# arduipi_test_board.net
KiCad netlist of a schematic drawn in EAGLE
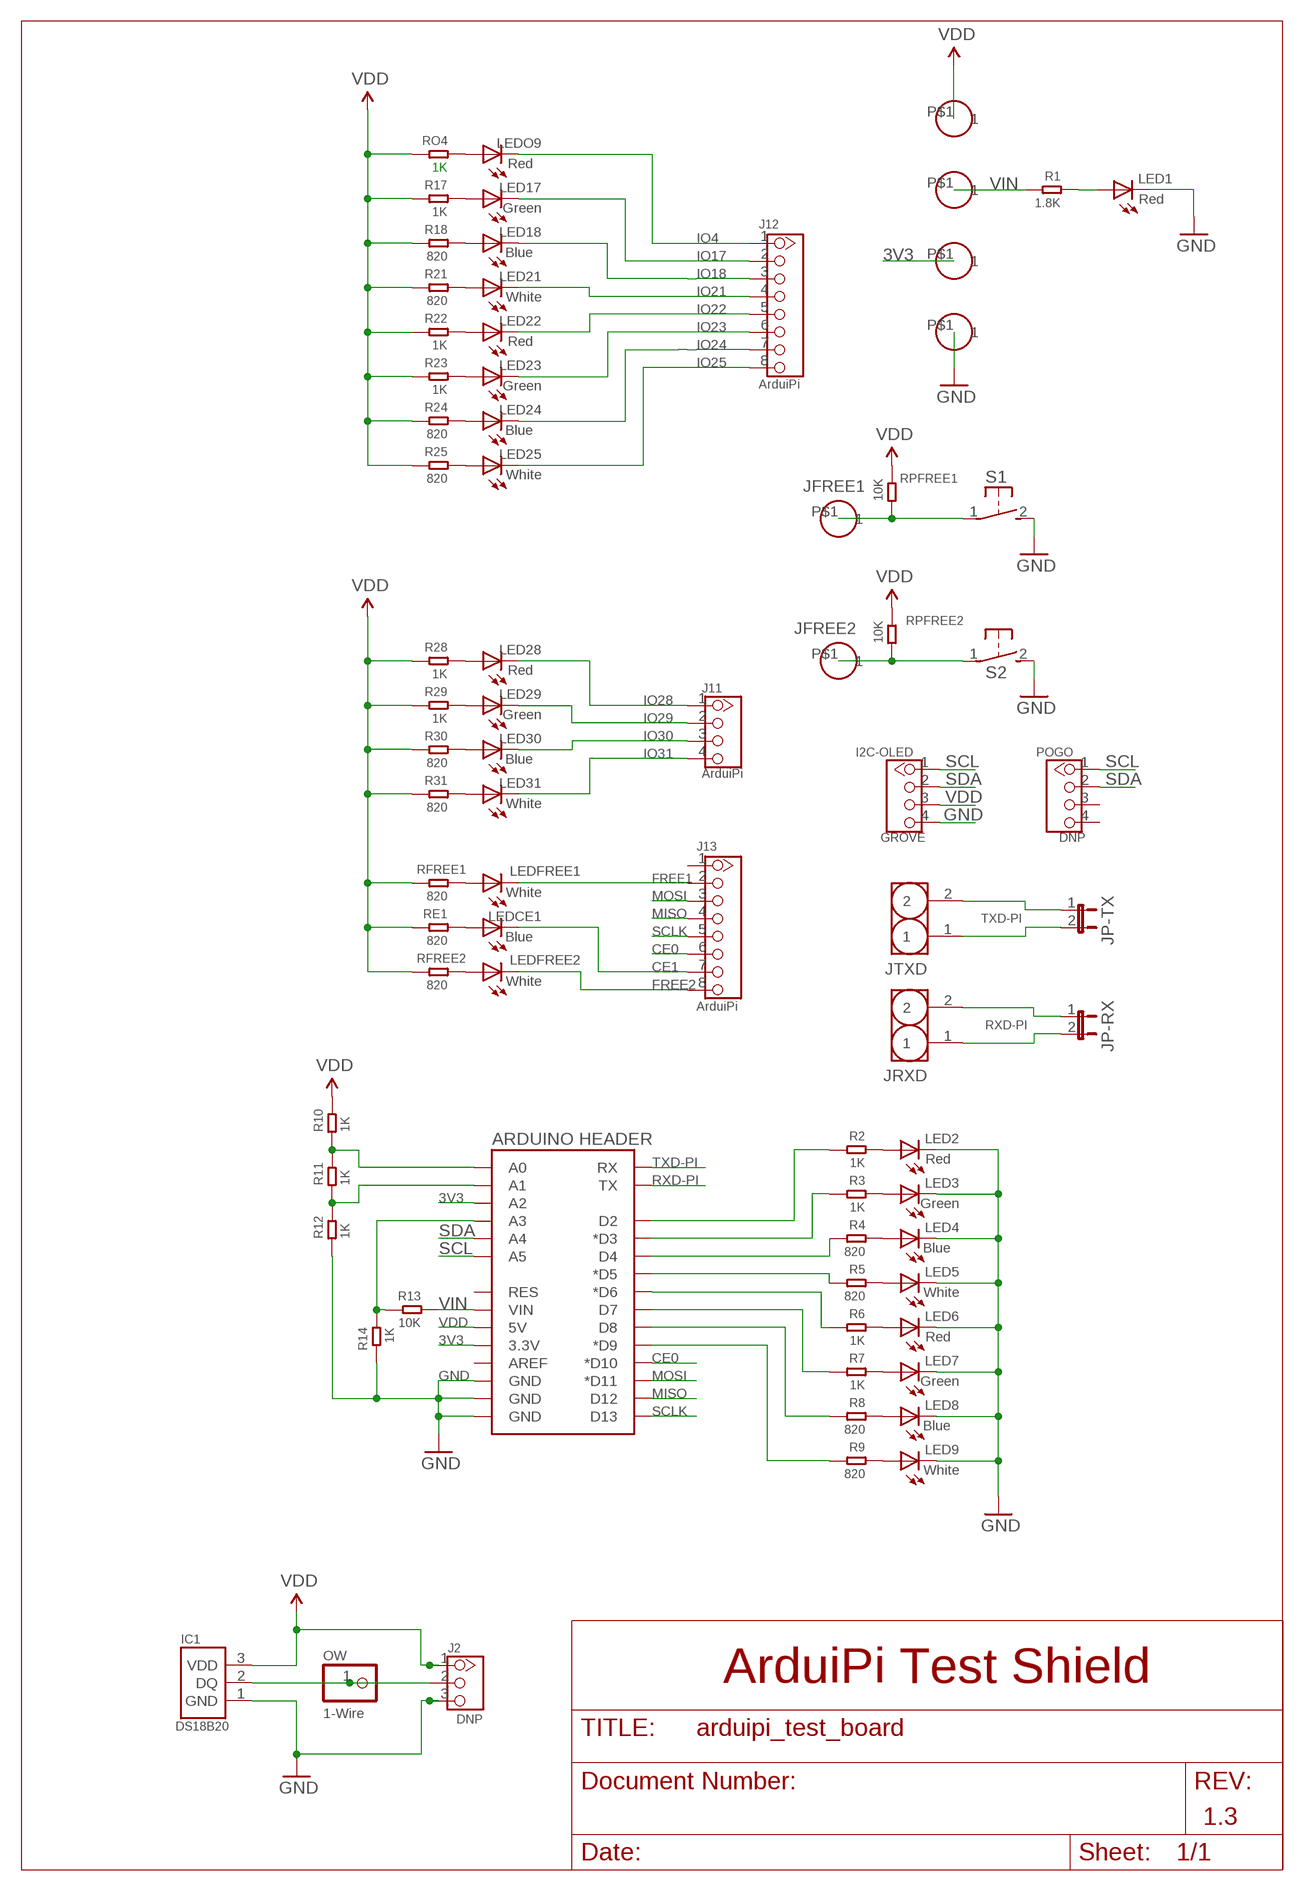
[diagram p0: schematic, sheet 1]

(export (version "E")
  (design (tool "Eeschema 10.0.6"))
  (components
    (comp (ref "3V3")
      (value "HEADER-1P-32")
      (footprint "eagle-import:1P-60_32MIL")
      (libsource (lib "eagle-import") (part "HEADER-1P-32"))
    )
    (comp (ref "GND")
      (value "HEADER-1P-32")
      (footprint "eagle-import:1P-60_32MIL")
      (libsource (lib "eagle-import") (part "HEADER-1P-32"))
    )
    (comp (ref "I2C-OLED")
      (value "GROVE")
      (footprint "eagle-import:4P-LEADED-2.0")
      (libsource (lib "eagle-import") (part "TWIG-2.0-LEADED"))
    )
    (comp (ref "IC1")
      (value "DS18B20")
      (footprint "eagle-import:TO-92-TRIANGLE")
      (libsource (lib "eagle-import") (part "SENSOR-DS18B20"))
    )
    (comp (ref "J2")
      (value "DNP")
      (footprint "eagle-import:3P-2.54")
      (libsource (lib "eagle-import") (part "HEADER-3P-2.54"))
    )
    (comp (ref "J11")
      (value "ArduiPi")
      (footprint "eagle-import:4P-2.54-80_40MIL")
      (libsource (lib "eagle-import") (part "HEADER-4P-80/40MIL"))
    )
    (comp (ref "J12")
      (value "ArduiPi")
      (footprint "eagle-import:8P-2.54-80_40MIL")
      (libsource (lib "eagle-import") (part "HEADER-8P-80/40MIL"))
    )
    (comp (ref "J13")
      (value "ArduiPi")
      (footprint "eagle-import:8P-2.54-80_40MIL")
      (libsource (lib "eagle-import") (part "HEADER-8P-80/40MIL"))
    )
    (comp (ref "JFREE1")
      (value "HEADER-1P-32")
      (footprint "eagle-import:1P-60_32MIL")
      (libsource (lib "eagle-import") (part "HEADER-1P-32"))
    )
    (comp (ref "JFREE2")
      (value "HEADER-1P-32")
      (footprint "eagle-import:1P-60_32MIL")
      (libsource (lib "eagle-import") (part "HEADER-1P-32"))
    )
    (comp (ref "JP-RX")
      (value "JUMPER-2PTH")
      (footprint "eagle-import:1X02")
      (libsource (lib "eagle-import") (part "JUMPER-2PTH"))
    )
    (comp (ref "JP-TX")
      (value "JUMPER-2PTH")
      (footprint "eagle-import:1X02")
      (libsource (lib "eagle-import") (part "JUMPER-2PTH"))
    )
    (comp (ref "JRXD")
      (value "J2")
      (footprint "eagle-import:2P-2.54")
      (libsource (lib "eagle-import") (part "HEADER-2P-2.54"))
    )
    (comp (ref "JTXD")
      (value "J1")
      (footprint "eagle-import:2P-2.54")
      (libsource (lib "eagle-import") (part "HEADER-2P-2.54"))
    )
    (comp (ref "LED1")
      (value "Red")
      (footprint "eagle-import:LED3MM")
      (libsource (lib "eagle-import") (part "LED3MM"))
    )
    (comp (ref "LED2")
      (value "Red")
      (footprint "eagle-import:LED3MM")
      (libsource (lib "eagle-import") (part "LED3MM"))
    )
    (comp (ref "LED3")
      (value "Green")
      (footprint "eagle-import:LED3MM")
      (libsource (lib "eagle-import") (part "LED3MM"))
    )
    (comp (ref "LED4")
      (value "Blue")
      (footprint "eagle-import:LED3MM")
      (libsource (lib "eagle-import") (part "LED3MM"))
    )
    (comp (ref "LED5")
      (value "White")
      (footprint "eagle-import:LED3MM")
      (libsource (lib "eagle-import") (part "LED3MM"))
    )
    (comp (ref "LED6")
      (value "Red")
      (footprint "eagle-import:LED3MM")
      (libsource (lib "eagle-import") (part "LED3MM"))
    )
    (comp (ref "LED7")
      (value "Green")
      (footprint "eagle-import:LED3MM")
      (libsource (lib "eagle-import") (part "LED3MM"))
    )
    (comp (ref "LED8")
      (value "Blue")
      (footprint "eagle-import:LED3MM")
      (libsource (lib "eagle-import") (part "LED3MM"))
    )
    (comp (ref "LED9")
      (value "White")
      (footprint "eagle-import:LED3MM")
      (libsource (lib "eagle-import") (part "LED3MM"))
    )
    (comp (ref "LED17")
      (value "Green")
      (footprint "eagle-import:LED3MM")
      (libsource (lib "eagle-import") (part "LED3MM"))
    )
    (comp (ref "LED18")
      (value "Blue")
      (footprint "eagle-import:LED3MM")
      (libsource (lib "eagle-import") (part "LED3MM"))
    )
    (comp (ref "LED21")
      (value "White")
      (footprint "eagle-import:LED3MM")
      (libsource (lib "eagle-import") (part "LED3MM"))
    )
    (comp (ref "LED22")
      (value "Red")
      (footprint "eagle-import:LED3MM")
      (libsource (lib "eagle-import") (part "LED3MM"))
    )
    (comp (ref "LED23")
      (value "Green")
      (footprint "eagle-import:LED3MM")
      (libsource (lib "eagle-import") (part "LED3MM"))
    )
    (comp (ref "LED24")
      (value "Blue")
      (footprint "eagle-import:LED3MM")
      (libsource (lib "eagle-import") (part "LED3MM"))
    )
    (comp (ref "LED25")
      (value "White")
      (footprint "eagle-import:LED3MM")
      (libsource (lib "eagle-import") (part "LED3MM"))
    )
    (comp (ref "LED28")
      (value "Red")
      (footprint "eagle-import:LED3MM")
      (libsource (lib "eagle-import") (part "LED3MM"))
    )
    (comp (ref "LED29")
      (value "Green")
      (footprint "eagle-import:LED3MM")
      (libsource (lib "eagle-import") (part "LED3MM"))
    )
    (comp (ref "LED30")
      (value "Blue")
      (footprint "eagle-import:LED3MM")
      (libsource (lib "eagle-import") (part "LED3MM"))
    )
    (comp (ref "LED31")
      (value "White")
      (footprint "eagle-import:LED3MM")
      (libsource (lib "eagle-import") (part "LED3MM"))
    )
    (comp (ref "LEDCE1")
      (value "Blue")
      (footprint "eagle-import:LED3MM")
      (libsource (lib "eagle-import") (part "LED3MM"))
    )
    (comp (ref "LEDFREE1")
      (value "White")
      (footprint "eagle-import:LED3MM")
      (libsource (lib "eagle-import") (part "LED3MM"))
    )
    (comp (ref "LEDFREE2")
      (value "White")
      (footprint "eagle-import:LED3MM")
      (libsource (lib "eagle-import") (part "LED3MM"))
    )
    (comp (ref "LEDO9")
      (value "Red")
      (footprint "eagle-import:LED3MM")
      (libsource (lib "eagle-import") (part "LED3MM"))
    )
    (comp (ref "OW")
      (value "1-Wire")
      (footprint "eagle-import:1X01")
      (libsource (lib "eagle-import") (part "PINHD-1X1"))
    )
    (comp (ref "POGO")
      (value "DNP")
      (footprint "eagle-import:4P-LEADED-2.0")
      (libsource (lib "eagle-import") (part "TWIG-2.0-LEADED"))
    )
    (comp (ref "R1")
      (value "1.8K")
      (footprint "eagle-import:0204_7")
      (libsource (lib "eagle-import") (part "R-0204/7"))
    )
    (comp (ref "R2")
      (value "1K")
      (footprint "eagle-import:0204_7")
      (libsource (lib "eagle-import") (part "R-0204/7"))
    )
    (comp (ref "R3")
      (value "1K")
      (footprint "eagle-import:0204_7")
      (libsource (lib "eagle-import") (part "R-0204/7"))
    )
    (comp (ref "R4")
      (value "820")
      (footprint "eagle-import:0204_7")
      (libsource (lib "eagle-import") (part "R-0204/7"))
    )
    (comp (ref "R5")
      (value "820")
      (footprint "eagle-import:0204_7")
      (libsource (lib "eagle-import") (part "R-0204/7"))
    )
    (comp (ref "R6")
      (value "1K")
      (footprint "eagle-import:0204_7")
      (libsource (lib "eagle-import") (part "R-0204/7"))
    )
    (comp (ref "R7")
      (value "1K")
      (footprint "eagle-import:0204_7")
      (libsource (lib "eagle-import") (part "R-0204/7"))
    )
    (comp (ref "R8")
      (value "820")
      (footprint "eagle-import:0204_7")
      (libsource (lib "eagle-import") (part "R-0204/7"))
    )
    (comp (ref "R9")
      (value "820")
      (footprint "eagle-import:0204_7")
      (libsource (lib "eagle-import") (part "R-0204/7"))
    )
    (comp (ref "R10")
      (value "1K")
      (footprint "eagle-import:0204_7")
      (libsource (lib "eagle-import") (part "R-0204/7"))
    )
    (comp (ref "R11")
      (value "1K")
      (footprint "eagle-import:0204_7")
      (libsource (lib "eagle-import") (part "R-0204/7"))
    )
    (comp (ref "R12")
      (value "1K")
      (footprint "eagle-import:0204_7")
      (libsource (lib "eagle-import") (part "R-0204/7"))
    )
    (comp (ref "R13")
      (value "10K")
      (footprint "eagle-import:0204_7")
      (libsource (lib "eagle-import") (part "R-0204/7"))
    )
    (comp (ref "R14")
      (value "1K")
      (footprint "eagle-import:0204_7")
      (libsource (lib "eagle-import") (part "R-0204/7"))
    )
    (comp (ref "R17")
      (value "1K")
      (footprint "eagle-import:0204_7")
      (libsource (lib "eagle-import") (part "R-0204/7"))
    )
    (comp (ref "R18")
      (value "820")
      (footprint "eagle-import:0204_7")
      (libsource (lib "eagle-import") (part "R-0204/7"))
    )
    (comp (ref "R21")
      (value "820")
      (footprint "eagle-import:0204_7")
      (libsource (lib "eagle-import") (part "R-0204/7"))
    )
    (comp (ref "R22")
      (value "1K")
      (footprint "eagle-import:0204_7")
      (libsource (lib "eagle-import") (part "R-0204/7"))
    )
    (comp (ref "R23")
      (value "1K")
      (footprint "eagle-import:0204_7")
      (libsource (lib "eagle-import") (part "R-0204/7"))
    )
    (comp (ref "R24")
      (value "820")
      (footprint "eagle-import:0204_7")
      (libsource (lib "eagle-import") (part "R-0204/7"))
    )
    (comp (ref "R25")
      (value "820")
      (footprint "eagle-import:0204_7")
      (libsource (lib "eagle-import") (part "R-0204/7"))
    )
    (comp (ref "R28")
      (value "1K")
      (footprint "eagle-import:0204_7")
      (libsource (lib "eagle-import") (part "R-0204/7"))
    )
    (comp (ref "R29")
      (value "1K")
      (footprint "eagle-import:0204_7")
      (libsource (lib "eagle-import") (part "R-0204/7"))
    )
    (comp (ref "R30")
      (value "820")
      (footprint "eagle-import:0204_7")
      (libsource (lib "eagle-import") (part "R-0204/7"))
    )
    (comp (ref "R31")
      (value "820")
      (footprint "eagle-import:0204_7")
      (libsource (lib "eagle-import") (part "R-0204/7"))
    )
    (comp (ref "RE1")
      (value "820")
      (footprint "eagle-import:0204_7")
      (libsource (lib "eagle-import") (part "R-0204/7"))
    )
    (comp (ref "RFREE1")
      (value "820")
      (footprint "eagle-import:0204_7")
      (libsource (lib "eagle-import") (part "R-0204/7"))
    )
    (comp (ref "RFREE2")
      (value "820")
      (footprint "eagle-import:0204_7")
      (libsource (lib "eagle-import") (part "R-0204/7"))
    )
    (comp (ref "RO4")
      (value "1K")
      (footprint "eagle-import:0204_7")
      (libsource (lib "eagle-import") (part "R-0204/7"))
    )
    (comp (ref "RPFREE1")
      (value "10K")
      (footprint "eagle-import:0204_7")
      (libsource (lib "eagle-import") (part "R-0204/7"))
    )
    (comp (ref "RPFREE2")
      (value "10K")
      (footprint "eagle-import:0204_7")
      (libsource (lib "eagle-import") (part "R-0204/7"))
    )
    (comp (ref "S1")
      (value "DTS-3")
      (footprint "eagle-import:DTS-3")
      (libsource (lib "eagle-import") (part "DTS-3"))
    )
    (comp (ref "S2")
      (value "DTS-3")
      (footprint "eagle-import:DTS-3")
      (libsource (lib "eagle-import") (part "DTS-3"))
    )
    (comp (ref "U1")
      (value "ARDUINO HEADER")
      (footprint "eagle-import:DUEMILANOVE_VIAS")
      (libsource (lib "eagle-import") (part "ARDUINO_SHIELDNO_SILK"))
    )
    (comp (ref "VDD")
      (value "HEADER-1P-32")
      (footprint "eagle-import:1P-60_32MIL")
      (libsource (lib "eagle-import") (part "HEADER-1P-32"))
    )
    (comp (ref "VIN")
      (value "HEADER-1P-32")
      (footprint "eagle-import:1P-60_32MIL")
      (libsource (lib "eagle-import") (part "HEADER-1P-32"))
    )
  )
  (nets
    (net (code "1") (name "/3V3") (class "Default")
      (node (ref "3V3") (pin "P$1") (pinfunction "1_P$1") (pintype "bidirectional"))
      (node (ref "U1") (pin "3.3V") (pinfunction "3.3V_3.3V") (pintype "bidirectional"))
      (node (ref "U1") (pin "A2") (pinfunction "A2_A2") (pintype "bidirectional"))
    )
    (net (code "2") (name "/CE0") (class "Default")
      (node (ref "J13") (pin "6") (pinfunction "6_6") (pintype "bidirectional"))
      (node (ref "U1") (pin "D10") (pinfunction "*D10_D10") (pintype "bidirectional"))
    )
    (net (code "3") (name "/CE1") (class "Default")
      (node (ref "J13") (pin "7") (pinfunction "7_7") (pintype "bidirectional"))
      (node (ref "LEDCE1") (pin "K") (pinfunction "C_K") (pintype "passive"))
    )
    (net (code "4") (name "/FREE1") (class "Default")
      (node (ref "J13") (pin "2") (pinfunction "2_2") (pintype "bidirectional"))
      (node (ref "LEDFREE1") (pin "K") (pinfunction "C_K") (pintype "passive"))
    )
    (net (code "5") (name "/FREE2") (class "Default")
      (node (ref "J13") (pin "8") (pinfunction "8_8") (pintype "bidirectional"))
      (node (ref "LEDFREE2") (pin "K") (pinfunction "C_K") (pintype "passive"))
    )
    (net (code "6") (name "/IO4") (class "Default")
      (node (ref "J12") (pin "1") (pinfunction "1_1") (pintype "bidirectional"))
      (node (ref "LEDO9") (pin "K") (pinfunction "C_K") (pintype "passive"))
    )
    (net (code "7") (name "/IO17") (class "Default")
      (node (ref "J12") (pin "2") (pinfunction "2_2") (pintype "bidirectional"))
      (node (ref "LED17") (pin "K") (pinfunction "C_K") (pintype "passive"))
    )
    (net (code "8") (name "/IO18") (class "Default")
      (node (ref "J12") (pin "3") (pinfunction "3_3") (pintype "bidirectional"))
      (node (ref "LED18") (pin "K") (pinfunction "C_K") (pintype "passive"))
    )
    (net (code "9") (name "/IO21") (class "Default")
      (node (ref "J12") (pin "4") (pinfunction "4_4") (pintype "bidirectional"))
      (node (ref "LED21") (pin "K") (pinfunction "C_K") (pintype "passive"))
    )
    (net (code "10") (name "/IO22") (class "Default")
      (node (ref "J12") (pin "5") (pinfunction "5_5") (pintype "bidirectional"))
      (node (ref "LED22") (pin "K") (pinfunction "C_K") (pintype "passive"))
    )
    (net (code "11") (name "/IO23") (class "Default")
      (node (ref "J12") (pin "6") (pinfunction "6_6") (pintype "bidirectional"))
      (node (ref "LED23") (pin "K") (pinfunction "C_K") (pintype "passive"))
    )
    (net (code "12") (name "/IO24") (class "Default")
      (node (ref "J12") (pin "7") (pinfunction "7_7") (pintype "bidirectional"))
      (node (ref "LED24") (pin "K") (pinfunction "C_K") (pintype "passive"))
    )
    (net (code "13") (name "/IO25") (class "Default")
      (node (ref "J12") (pin "8") (pinfunction "8_8") (pintype "bidirectional"))
      (node (ref "LED25") (pin "K") (pinfunction "C_K") (pintype "passive"))
    )
    (net (code "14") (name "/IO28") (class "Default")
      (node (ref "J11") (pin "1") (pinfunction "P$1_1") (pintype "bidirectional"))
      (node (ref "LED28") (pin "K") (pinfunction "C_K") (pintype "passive"))
    )
    (net (code "15") (name "/IO29") (class "Default")
      (node (ref "J11") (pin "2") (pinfunction "P$2_2") (pintype "bidirectional"))
      (node (ref "LED29") (pin "K") (pinfunction "C_K") (pintype "passive"))
    )
    (net (code "16") (name "/IO30") (class "Default")
      (node (ref "J11") (pin "3") (pinfunction "P$3_3") (pintype "bidirectional"))
      (node (ref "LED30") (pin "K") (pinfunction "C_K") (pintype "passive"))
    )
    (net (code "17") (name "/IO31") (class "Default")
      (node (ref "J11") (pin "4") (pinfunction "P$4_4") (pintype "bidirectional"))
      (node (ref "LED31") (pin "K") (pinfunction "C_K") (pintype "passive"))
    )
    (net (code "18") (name "/MISO") (class "Default")
      (node (ref "J13") (pin "4") (pinfunction "4_4") (pintype "bidirectional"))
      (node (ref "U1") (pin "D12") (pinfunction "D12_D12") (pintype "bidirectional"))
    )
    (net (code "19") (name "/MOSI") (class "Default")
      (node (ref "J13") (pin "3") (pinfunction "3_3") (pintype "bidirectional"))
      (node (ref "U1") (pin "D11") (pinfunction "*D11_D11") (pintype "bidirectional"))
    )
    (net (code "20") (name "/RXD-PI") (class "Default")
      (node (ref "JP-RX") (pin "1") (pinfunction "1_1") (pintype "passive"))
      (node (ref "JRXD") (pin "2") (pinfunction "2_2") (pintype "bidirectional"))
      (node (ref "U1") (pin "TX") (pinfunction "TX_TX") (pintype "bidirectional"))
    )
    (net (code "21") (name "/SCL") (class "Default")
      (node (ref "I2C-OLED") (pin "1") (pinfunction "1_1") (pintype "bidirectional"))
      (node (ref "POGO") (pin "1") (pinfunction "1_1") (pintype "bidirectional"))
      (node (ref "U1") (pin "A5") (pinfunction "A5_A5") (pintype "bidirectional"))
    )
    (net (code "22") (name "/SCLK") (class "Default")
      (node (ref "J13") (pin "5") (pinfunction "5_5") (pintype "bidirectional"))
      (node (ref "U1") (pin "D13") (pinfunction "D13_D13") (pintype "bidirectional"))
    )
    (net (code "23") (name "/SDA") (class "Default")
      (node (ref "I2C-OLED") (pin "2") (pinfunction "2_2") (pintype "bidirectional"))
      (node (ref "POGO") (pin "2") (pinfunction "2_2") (pintype "bidirectional"))
      (node (ref "U1") (pin "A4") (pinfunction "A4_A4") (pintype "bidirectional"))
    )
    (net (code "24") (name "/TXD-PI") (class "Default")
      (node (ref "JP-TX") (pin "1") (pinfunction "1_1") (pintype "passive"))
      (node (ref "JTXD") (pin "2") (pinfunction "2_2") (pintype "bidirectional"))
      (node (ref "U1") (pin "RX") (pinfunction "RX_RX") (pintype "bidirectional"))
    )
    (net (code "25") (name "/VIN") (class "Default")
      (node (ref "R1") (pin "2") (pinfunction "2_2") (pintype "passive"))
      (node (ref "R13") (pin "1") (pinfunction "1_1") (pintype "passive"))
      (node (ref "U1") (pin "VIN") (pinfunction "VIN_VIN") (pintype "bidirectional"))
      (node (ref "VIN") (pin "P$1") (pinfunction "1_P$1") (pintype "bidirectional"))
    )
    (net (code "26") (name "GND") (class "Default")
      (node (ref "GND") (pin "P$1") (pinfunction "1_P$1") (pintype "bidirectional"))
      (node (ref "I2C-OLED") (pin "4") (pinfunction "4_4") (pintype "bidirectional"))
      (node (ref "IC1") (pin "1") (pinfunction "GND_1") (pintype "bidirectional"))
      (node (ref "J2") (pin "3") (pinfunction "P$3_3") (pintype "bidirectional"))
      (node (ref "LED1") (pin "K") (pinfunction "C_K") (pintype "passive"))
      (node (ref "LED2") (pin "K") (pinfunction "C_K") (pintype "passive"))
      (node (ref "LED3") (pin "K") (pinfunction "C_K") (pintype "passive"))
      (node (ref "LED4") (pin "K") (pinfunction "C_K") (pintype "passive"))
      (node (ref "LED5") (pin "K") (pinfunction "C_K") (pintype "passive"))
      (node (ref "LED6") (pin "K") (pinfunction "C_K") (pintype "passive"))
      (node (ref "LED7") (pin "K") (pinfunction "C_K") (pintype "passive"))
      (node (ref "LED8") (pin "K") (pinfunction "C_K") (pintype "passive"))
      (node (ref "LED9") (pin "K") (pinfunction "C_K") (pintype "passive"))
      (node (ref "R12") (pin "1") (pinfunction "1_1") (pintype "passive"))
      (node (ref "R14") (pin "2") (pinfunction "2_2") (pintype "passive"))
      (node (ref "S1") (pin "2") (pinfunction "2_2") (pintype "passive"))
      (node (ref "S2") (pin "2") (pinfunction "2_2") (pintype "passive"))
      (node (ref "U1") (pin "GND@0") (pinfunction "GND_GND@0") (pintype "bidirectional"))
      (node (ref "U1") (pin "GND@1") (pinfunction "GND_GND@1") (pintype "bidirectional"))
      (node (ref "U1") (pin "GND@2") (pinfunction "GND_GND@2") (pintype "bidirectional"))
    )
    (net (code "27") (name "Net-(IC1-DQ)") (class "Default")
      (node (ref "IC1") (pin "2") (pinfunction "DQ_2") (pintype "bidirectional"))
      (node (ref "J2") (pin "2") (pinfunction "P$2_2") (pintype "bidirectional"))
      (node (ref "OW") (pin "1") (pinfunction "1_1") (pintype "passive"))
    )
    (net (code "28") (name "Net-(JFREE1-1)") (class "Default")
      (node (ref "JFREE1") (pin "P$1") (pinfunction "1_P$1") (pintype "bidirectional"))
      (node (ref "RPFREE1") (pin "2") (pinfunction "2_2") (pintype "passive"))
      (node (ref "S1") (pin "1") (pinfunction "1_1") (pintype "passive"))
    )
    (net (code "29") (name "Net-(JFREE2-1)") (class "Default")
      (node (ref "JFREE2") (pin "P$1") (pinfunction "1_P$1") (pintype "bidirectional"))
      (node (ref "RPFREE2") (pin "1") (pinfunction "1_1") (pintype "passive"))
      (node (ref "S2") (pin "1") (pinfunction "1_1") (pintype "passive"))
    )
    (net (code "30") (name "Net-(JP-RX-Pad2)") (class "Default")
      (node (ref "JP-RX") (pin "2") (pinfunction "2_2") (pintype "passive"))
      (node (ref "JRXD") (pin "1") (pinfunction "1_1") (pintype "bidirectional"))
    )
    (net (code "31") (name "Net-(JP-TX-Pad2)") (class "Default")
      (node (ref "JP-TX") (pin "2") (pinfunction "2_2") (pintype "passive"))
      (node (ref "JTXD") (pin "1") (pinfunction "1_1") (pintype "bidirectional"))
    )
    (net (code "32") (name "Net-(LED1-PadA)") (class "Default")
      (node (ref "LED1") (pin "A") (pinfunction "A_A") (pintype "passive"))
      (node (ref "R1") (pin "1") (pinfunction "1_1") (pintype "passive"))
    )
    (net (code "33") (name "Net-(LED2-PadA)") (class "Default")
      (node (ref "LED2") (pin "A") (pinfunction "A_A") (pintype "passive"))
      (node (ref "R2") (pin "1") (pinfunction "1_1") (pintype "passive"))
    )
    (net (code "34") (name "Net-(LED3-PadA)") (class "Default")
      (node (ref "LED3") (pin "A") (pinfunction "A_A") (pintype "passive"))
      (node (ref "R3") (pin "1") (pinfunction "1_1") (pintype "passive"))
    )
    (net (code "35") (name "Net-(LED4-PadA)") (class "Default")
      (node (ref "LED4") (pin "A") (pinfunction "A_A") (pintype "passive"))
      (node (ref "R4") (pin "1") (pinfunction "1_1") (pintype "passive"))
    )
    (net (code "36") (name "Net-(LED5-PadA)") (class "Default")
      (node (ref "LED5") (pin "A") (pinfunction "A_A") (pintype "passive"))
      (node (ref "R5") (pin "1") (pinfunction "1_1") (pintype "passive"))
    )
    (net (code "37") (name "Net-(LED6-PadA)") (class "Default")
      (node (ref "LED6") (pin "A") (pinfunction "A_A") (pintype "passive"))
      (node (ref "R6") (pin "1") (pinfunction "1_1") (pintype "passive"))
    )
    (net (code "38") (name "Net-(LED7-PadA)") (class "Default")
      (node (ref "LED7") (pin "A") (pinfunction "A_A") (pintype "passive"))
      (node (ref "R7") (pin "1") (pinfunction "1_1") (pintype "passive"))
    )
    (net (code "39") (name "Net-(LED8-PadA)") (class "Default")
      (node (ref "LED8") (pin "A") (pinfunction "A_A") (pintype "passive"))
      (node (ref "R8") (pin "1") (pinfunction "1_1") (pintype "passive"))
    )
    (net (code "40") (name "Net-(LED9-PadA)") (class "Default")
      (node (ref "LED9") (pin "A") (pinfunction "A_A") (pintype "passive"))
      (node (ref "R9") (pin "1") (pinfunction "1_1") (pintype "passive"))
    )
    (net (code "41") (name "Net-(LED17-PadA)") (class "Default")
      (node (ref "LED17") (pin "A") (pinfunction "A_A") (pintype "passive"))
      (node (ref "R17") (pin "1") (pinfunction "1_1") (pintype "passive"))
    )
    (net (code "42") (name "Net-(LED18-PadA)") (class "Default")
      (node (ref "LED18") (pin "A") (pinfunction "A_A") (pintype "passive"))
      (node (ref "R18") (pin "1") (pinfunction "1_1") (pintype "passive"))
    )
    (net (code "43") (name "Net-(LED21-PadA)") (class "Default")
      (node (ref "LED21") (pin "A") (pinfunction "A_A") (pintype "passive"))
      (node (ref "R21") (pin "1") (pinfunction "1_1") (pintype "passive"))
    )
    (net (code "44") (name "Net-(LED22-PadA)") (class "Default")
      (node (ref "LED22") (pin "A") (pinfunction "A_A") (pintype "passive"))
      (node (ref "R22") (pin "1") (pinfunction "1_1") (pintype "passive"))
    )
    (net (code "45") (name "Net-(LED23-PadA)") (class "Default")
      (node (ref "LED23") (pin "A") (pinfunction "A_A") (pintype "passive"))
      (node (ref "R23") (pin "1") (pinfunction "1_1") (pintype "passive"))
    )
    (net (code "46") (name "Net-(LED24-PadA)") (class "Default")
      (node (ref "LED24") (pin "A") (pinfunction "A_A") (pintype "passive"))
      (node (ref "R24") (pin "1") (pinfunction "1_1") (pintype "passive"))
    )
    (net (code "47") (name "Net-(LED25-PadA)") (class "Default")
      (node (ref "LED25") (pin "A") (pinfunction "A_A") (pintype "passive"))
      (node (ref "R25") (pin "1") (pinfunction "1_1") (pintype "passive"))
    )
    (net (code "48") (name "Net-(LED28-PadA)") (class "Default")
      (node (ref "LED28") (pin "A") (pinfunction "A_A") (pintype "passive"))
      (node (ref "R28") (pin "1") (pinfunction "1_1") (pintype "passive"))
    )
    (net (code "49") (name "Net-(LED29-PadA)") (class "Default")
      (node (ref "LED29") (pin "A") (pinfunction "A_A") (pintype "passive"))
      (node (ref "R29") (pin "1") (pinfunction "1_1") (pintype "passive"))
    )
    (net (code "50") (name "Net-(LED30-PadA)") (class "Default")
      (node (ref "LED30") (pin "A") (pinfunction "A_A") (pintype "passive"))
      (node (ref "R30") (pin "1") (pinfunction "1_1") (pintype "passive"))
    )
    (net (code "51") (name "Net-(LED31-PadA)") (class "Default")
      (node (ref "LED31") (pin "A") (pinfunction "A_A") (pintype "passive"))
      (node (ref "R31") (pin "1") (pinfunction "1_1") (pintype "passive"))
    )
    (net (code "52") (name "Net-(LEDCE1-PadA)") (class "Default")
      (node (ref "LEDCE1") (pin "A") (pinfunction "A_A") (pintype "passive"))
      (node (ref "RE1") (pin "1") (pinfunction "1_1") (pintype "passive"))
    )
    (net (code "53") (name "Net-(LEDFREE1-PadA)") (class "Default")
      (node (ref "LEDFREE1") (pin "A") (pinfunction "A_A") (pintype "passive"))
      (node (ref "RFREE1") (pin "1") (pinfunction "1_1") (pintype "passive"))
    )
    (net (code "54") (name "Net-(LEDFREE2-PadA)") (class "Default")
      (node (ref "LEDFREE2") (pin "A") (pinfunction "A_A") (pintype "passive"))
      (node (ref "RFREE2") (pin "1") (pinfunction "1_1") (pintype "passive"))
    )
    (net (code "55") (name "Net-(LEDO9-PadA)") (class "Default")
      (node (ref "LEDO9") (pin "A") (pinfunction "A_A") (pintype "passive"))
      (node (ref "RO4") (pin "1") (pinfunction "1_1") (pintype "passive"))
    )
    (net (code "56") (name "Net-(R2-Pad2)") (class "Default")
      (node (ref "R2") (pin "2") (pinfunction "2_2") (pintype "passive"))
      (node (ref "U1") (pin "D2") (pinfunction "D2_D2") (pintype "bidirectional"))
    )
    (net (code "57") (name "Net-(R4-Pad2)") (class "Default")
      (node (ref "R4") (pin "2") (pinfunction "2_2") (pintype "passive"))
      (node (ref "U1") (pin "D4") (pinfunction "D4_D4") (pintype "bidirectional"))
    )
    (net (code "58") (name "Net-(R7-Pad2)") (class "Default")
      (node (ref "R7") (pin "2") (pinfunction "2_2") (pintype "passive"))
      (node (ref "U1") (pin "D7") (pinfunction "D7_D7") (pintype "bidirectional"))
    )
    (net (code "59") (name "Net-(R8-Pad2)") (class "Default")
      (node (ref "R8") (pin "2") (pinfunction "2_2") (pintype "passive"))
      (node (ref "U1") (pin "D8") (pinfunction "D8_D8") (pintype "bidirectional"))
    )
    (net (code "60") (name "Net-(R10-Pad1)") (class "Default")
      (node (ref "R10") (pin "1") (pinfunction "1_1") (pintype "passive"))
      (node (ref "R11") (pin "2") (pinfunction "2_2") (pintype "passive"))
      (node (ref "U1") (pin "A0") (pinfunction "A0_A0") (pintype "bidirectional"))
    )
    (net (code "61") (name "Net-(R11-Pad1)") (class "Default")
      (node (ref "R11") (pin "1") (pinfunction "1_1") (pintype "passive"))
      (node (ref "R12") (pin "2") (pinfunction "2_2") (pintype "passive"))
      (node (ref "U1") (pin "A1") (pinfunction "A1_A1") (pintype "bidirectional"))
    )
    (net (code "62") (name "Net-(R13-Pad2)") (class "Default")
      (node (ref "R13") (pin "2") (pinfunction "2_2") (pintype "passive"))
      (node (ref "R14") (pin "1") (pinfunction "1_1") (pintype "passive"))
      (node (ref "U1") (pin "A3") (pinfunction "A3_A3") (pintype "bidirectional"))
    )
    (net (code "63") (name "Net-(U1-*D3)") (class "Default")
      (node (ref "R3") (pin "2") (pinfunction "2_2") (pintype "passive"))
      (node (ref "U1") (pin "D3") (pinfunction "*D3_D3") (pintype "bidirectional"))
    )
    (net (code "64") (name "Net-(U1-*D5)") (class "Default")
      (node (ref "R5") (pin "2") (pinfunction "2_2") (pintype "passive"))
      (node (ref "U1") (pin "D5") (pinfunction "*D5_D5") (pintype "bidirectional"))
    )
    (net (code "65") (name "Net-(U1-*D6)") (class "Default")
      (node (ref "R6") (pin "2") (pinfunction "2_2") (pintype "passive"))
      (node (ref "U1") (pin "D6") (pinfunction "*D6_D6") (pintype "bidirectional"))
    )
    (net (code "66") (name "Net-(U1-*D9)") (class "Default")
      (node (ref "R9") (pin "2") (pinfunction "2_2") (pintype "passive"))
      (node (ref "U1") (pin "D9") (pinfunction "*D9_D9") (pintype "bidirectional"))
    )
    (net (code "67") (name "VDD") (class "Default")
      (node (ref "I2C-OLED") (pin "3") (pinfunction "3_3") (pintype "bidirectional"))
      (node (ref "IC1") (pin "3") (pinfunction "VDD_3") (pintype "bidirectional"))
      (node (ref "J2") (pin "1") (pinfunction "P$1_1") (pintype "bidirectional"))
      (node (ref "R10") (pin "2") (pinfunction "2_2") (pintype "passive"))
      (node (ref "R17") (pin "2") (pinfunction "2_2") (pintype "passive"))
      (node (ref "R18") (pin "2") (pinfunction "2_2") (pintype "passive"))
      (node (ref "R21") (pin "2") (pinfunction "2_2") (pintype "passive"))
      (node (ref "R22") (pin "2") (pinfunction "2_2") (pintype "passive"))
      (node (ref "R23") (pin "2") (pinfunction "2_2") (pintype "passive"))
      (node (ref "R24") (pin "2") (pinfunction "2_2") (pintype "passive"))
      (node (ref "R25") (pin "2") (pinfunction "2_2") (pintype "passive"))
      (node (ref "R28") (pin "2") (pinfunction "2_2") (pintype "passive"))
      (node (ref "R29") (pin "2") (pinfunction "2_2") (pintype "passive"))
      (node (ref "R30") (pin "2") (pinfunction "2_2") (pintype "passive"))
      (node (ref "R31") (pin "2") (pinfunction "2_2") (pintype "passive"))
      (node (ref "RE1") (pin "2") (pinfunction "2_2") (pintype "passive"))
      (node (ref "RFREE1") (pin "2") (pinfunction "2_2") (pintype "passive"))
      (node (ref "RFREE2") (pin "2") (pinfunction "2_2") (pintype "passive"))
      (node (ref "RO4") (pin "2") (pinfunction "2_2") (pintype "passive"))
      (node (ref "RPFREE1") (pin "1") (pinfunction "1_1") (pintype "passive"))
      (node (ref "RPFREE2") (pin "2") (pinfunction "2_2") (pintype "passive"))
      (node (ref "U1") (pin "5V") (pinfunction "5V_5V") (pintype "bidirectional"))
      (node (ref "VDD") (pin "P$1") (pinfunction "1_P$1") (pintype "bidirectional"))
    )
    (net (code "68") (name "unconnected-(J13-Pad1)") (class "Default")
      (node (ref "J13") (pin "1") (pinfunction "1_1") (pintype "bidirectional"))
    )
    (net (code "69") (name "unconnected-(POGO-Pad3)") (class "Default")
      (node (ref "POGO") (pin "3") (pinfunction "3_3") (pintype "bidirectional"))
    )
    (net (code "70") (name "unconnected-(POGO-Pad4)") (class "Default")
      (node (ref "POGO") (pin "4") (pinfunction "4_4") (pintype "bidirectional"))
    )
    (net (code "71") (name "unconnected-(U1-PadAREF)") (class "Default")
      (node (ref "U1") (pin "AREF") (pinfunction "AREF_AREF") (pintype "bidirectional"))
    )
    (net (code "72") (name "unconnected-(U1-PadRES)") (class "Default")
      (node (ref "U1") (pin "RES") (pinfunction "RES_RES") (pintype "bidirectional"))
    )
  )
)
